# S52.net
KiCad netlist of a schematic drawn in Altium Designer
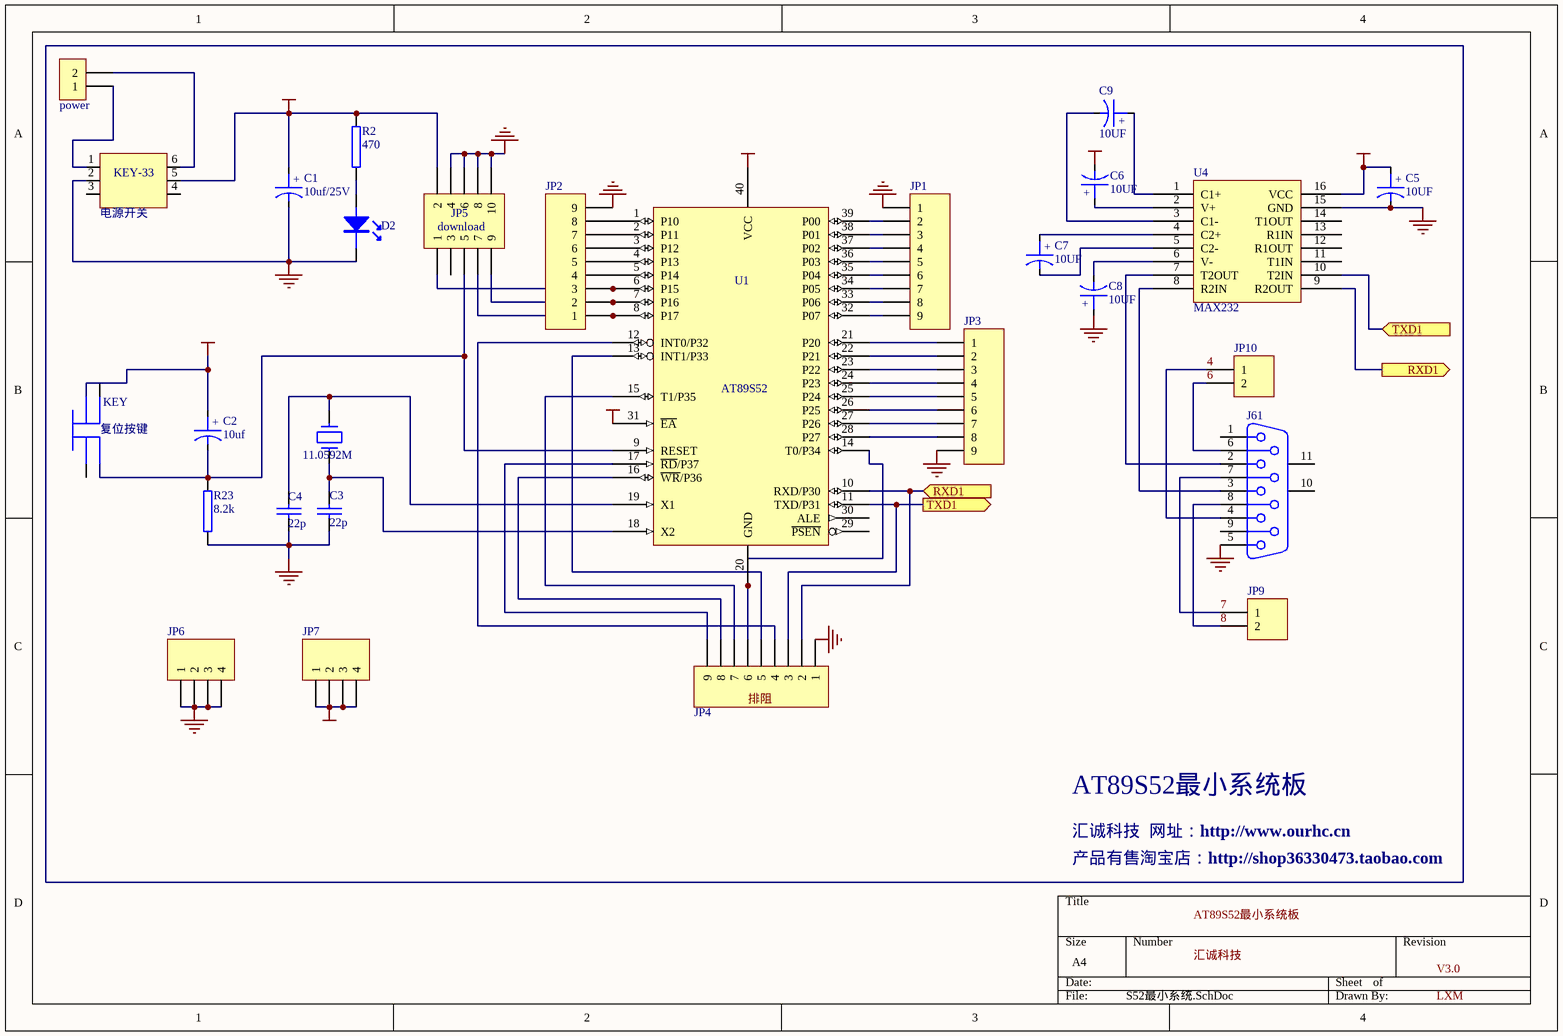
[diagram p0: S52最小系统.SchDoc]

(export (version "E")
  (design (tool "Eeschema 10.0.6"))
  (components
    (comp (ref "11") (value "power") (footprint "power1") (libsource (lib "OldCow1 (1)") (part "power")))
    (comp (ref "C1")
      (value "10uf/25V")
      (footprint "cap2")
      (description "Capacitor")
      (libsource (lib "OldCow1 (1)") (part "CAPACITOR POL"))
    )
    (comp (ref "C2")
      (value "10uf")
      (footprint "cap2")
      (description "Capacitor")
      (libsource (lib "*") (part "CAPACITOR POL"))
    )
    (comp (ref "C3")
      (value "22p")
      (footprint "RAD0.3")
      (description "Capacitor")
      (libsource (lib "*") (part "CAP"))
    )
    (comp (ref "C4")
      (value "22p")
      (footprint "RAD0.3")
      (description "Capacitor")
      (libsource (lib "*") (part "CAP"))
    )
    (comp (ref "C5")
      (value "10UF")
      (footprint "cap2")
      (description "Capacitor")
      (libsource (lib "*") (part "CAPACITOR POL"))
    )
    (comp (ref "C6")
      (value "10UF")
      (footprint "cap2")
      (description "Capacitor")
      (libsource (lib "*") (part "CAPACITOR POL"))
    )
    (comp (ref "C7")
      (value "10UF")
      (footprint "cap2")
      (description "Capacitor")
      (libsource (lib "*") (part "CAPACITOR POL"))
    )
    (comp (ref "C8")
      (value "10UF")
      (footprint "cap2")
      (description "Capacitor")
      (libsource (lib "*") (part "CAPACITOR POL"))
    )
    (comp (ref "C9")
      (value "10UF")
      (footprint "cap2")
      (description "Capacitor")
      (libsource (lib "*") (part "CAPACITOR POL"))
    )
    (comp (ref "D2") (value "LED") (footprint "LED") (libsource (lib "OldCow1 (1)") (part "LED")))
    (comp (ref "J61")
      (value "D Connector 9")
      (footprint "DSUB1.385-2H9")
      (description "Receptacle Assembly, 9 Position, Right Angle")
      (fields (field (name "PUBLISHER") "Altium Limited"))
      (libsource (lib "Miscellaneous Connectors") (part "D Connector 9"))
    )
    (comp (ref "JP1")
      (value "~")
      (footprint "HDR1X9")
      (description "Header, 9-Pin")
      (fields (field (name "PUBLISHER") "Altium Limited"))
      (libsource (lib "") (part "Header 9_2"))
    )
    (comp (ref "JP2")
      (value "~")
      (footprint "HDR1X9")
      (description "Header, 9-Pin")
      (fields (field (name "PUBLISHER") "Altium Limited"))
      (libsource (lib "") (part "Header 9_1"))
    )
    (comp (ref "JP3")
      (value "~")
      (footprint "HDR1X9")
      (description "Header, 9-Pin")
      (fields (field (name "PUBLISHER") "Altium Limited"))
      (libsource (lib "") (part "Header 9_2"))
    )
    (comp (ref "JP4")
      (value "~")
      (footprint "HDR1X9")
      (description "Header, 9-Pin")
      (fields (field (name "PUBLISHER") "Altium Limited"))
      (libsource (lib "Miscellaneous Connectors") (part "Header 9"))
    )
    (comp (ref "JP5")
      (value "download")
      (footprint "HDR2X5")
      (description "Header, 5-Pin, Dual row")
      (fields (field (name "PUBLISHER") "Altium Limited"))
      (libsource (lib "Miscellaneous Connectors") (part "Header 5X2"))
    )
    (comp (ref "JP6")
      (value "~")
      (footprint "HDR1X4")
      (description "Header, 4-Pin")
      (fields (field (name "PUBLISHER") "Altium Limited"))
      (libsource (lib "Miscellaneous Connectors") (part "Header 4"))
    )
    (comp (ref "JP7")
      (value "~")
      (footprint "HDR1X4")
      (description "Header, 4-Pin")
      (fields (field (name "PUBLISHER") "Altium Limited"))
      (libsource (lib "Miscellaneous Connectors") (part "Header 4"))
    )
    (comp (ref "JP9")
      (value "~")
      (footprint "HDR1X2")
      (description "Header, 2-Pin")
      (fields (field (name "PUBLISHER") "Altium Limited"))
      (libsource (lib "Miscellaneous Connectors") (part "Header 2"))
    )
    (comp (ref "JP10")
      (value "Header 3")
      (footprint "HDR1X2")
      (description "Header, 2-Pin")
      (fields (field (name "PUBLISHER") "Altium Limited"))
      (libsource (lib "Miscellaneous Connectors") (part "Header 2"))
    )
    (comp (ref "KEY")
      (value "复位按键")
      (footprint "KEY-1")
      (description "KEY")
      (libsource (lib "OldCow1 (1)") (part "KEY"))
    )
    (comp (ref "KEY-33") (value "电源开关") (footprint "KEY-2") (libsource (lib "OldCow1 (1)") (part "KEY-33")))
    (comp (ref "R2") (value "470") (footprint "AXIAL0.4") (libsource (lib "*") (part "RES2")))
    (comp (ref "R23") (value "8.2k") (footprint "AXIAL0.4") (libsource (lib "*") (part "RES2")))
    (comp (ref "U1") (value "AT89S52") (footprint "AT89S52Pid") (libsource (lib "OldCow1 (2)") (part "8051")))
    (comp (ref "U4") (value "MAX232") (footprint "DIP16") (libsource (lib "*") (part "MAX232")))
    (comp (ref "Y")
      (value "11.0592M")
      (footprint "CRYSTAL")
      (description "Crystal")
      (libsource (lib "*") (part "CRYSTAL"))
    )
  )
  (nets
    (net (code "1") (name "/4") (class "Default")
      (node (ref "J61") (pin "4") (pinfunction "4_4") (pintype "passive"))
      (node (ref "JP10") (pin "1") (pinfunction "1_1") (pintype "passive"))
    )
    (net (code "2") (name "/6") (class "Default")
      (node (ref "J61") (pin "6") (pinfunction "6_6") (pintype "passive"))
      (node (ref "JP10") (pin "2") (pinfunction "2_2") (pintype "passive"))
    )
    (net (code "3") (name "/7") (class "Default")
      (node (ref "J61") (pin "7") (pinfunction "7_7") (pintype "passive"))
      (node (ref "JP9") (pin "1") (pinfunction "1_1") (pintype "passive"))
    )
    (net (code "4") (name "/8") (class "Default")
      (node (ref "J61") (pin "8") (pinfunction "8_8") (pintype "passive"))
      (node (ref "JP9") (pin "2") (pinfunction "2_2") (pintype "passive"))
    )
    (net (code "8") (name "/RXD1") (class "Default")
      (node (ref "JP4") (pin "2") (pinfunction "2_2") (pintype "passive"))
      (node (ref "U1") (pin "10") (pinfunction "RXD/P30_10") (pintype "bidirectional"))
      (node (ref "U4") (pin "9") (pinfunction "R2OUT_9") (pintype "passive"))
    )
    (net (code "9") (name "/TXD1") (class "Default")
      (node (ref "JP4") (pin "3") (pinfunction "3_3") (pintype "passive"))
      (node (ref "U1") (pin "11") (pinfunction "TXD/P31_11") (pintype "bidirectional"))
      (node (ref "U4") (pin "10") (pinfunction "T2IN_10") (pintype "passive"))
    )
    (net (code "13") (name "GND") (class "Default")
      (node (ref "C1") (pin "2") (pinfunction "2_2") (pintype "passive"))
      (node (ref "C3") (pin "2") (pinfunction "2_2") (pintype "passive"))
      (node (ref "C4") (pin "2") (pinfunction "2_2") (pintype "passive"))
      (node (ref "C5") (pin "2") (pinfunction "2_2") (pintype "passive"))
      (node (ref "C8") (pin "1") (pinfunction "1_1") (pintype "passive"))
      (node (ref "D2") (pin "2") (pinfunction "K_2") (pintype "passive"))
      (node (ref "J61") (pin "5") (pinfunction "5_5") (pintype "passive"))
      (node (ref "JP1") (pin "1") (pinfunction "1_1") (pintype "passive"))
      (node (ref "JP2") (pin "9") (pinfunction "9_9") (pintype "passive"))
      (node (ref "JP3") (pin "9") (pinfunction "9_9") (pintype "passive"))
      (node (ref "JP4") (pin "1") (pinfunction "1_1") (pintype "passive"))
      (node (ref "JP5") (pin "10") (pinfunction "10_10") (pintype "passive"))
      (node (ref "JP5") (pin "4") (pinfunction "4_4") (pintype "passive"))
      (node (ref "JP5") (pin "6") (pinfunction "6_6") (pintype "passive"))
      (node (ref "JP5") (pin "8") (pinfunction "8_8") (pintype "passive"))
      (node (ref "JP6") (pin "1") (pinfunction "1_1") (pintype "passive"))
      (node (ref "JP6") (pin "2") (pinfunction "2_2") (pintype "passive"))
      (node (ref "JP6") (pin "3") (pinfunction "3_3") (pintype "passive"))
      (node (ref "JP6") (pin "4") (pinfunction "4_4") (pintype "passive"))
      (node (ref "KEY-33") (pin "2") (pintype "passive"))
      (node (ref "R23") (pin "2") (pinfunction "2_2") (pintype "passive"))
      (node (ref "U4") (pin "15") (pinfunction "GND_15") (pintype "passive"))
    )
    (net (code "14") (name "Net-(11-Pad1)") (class "Default")
      (node (ref "11") (pin "1") (pinfunction "1_1") (pintype "passive"))
      (node (ref "KEY-33") (pin "1") (pintype "passive"))
    )
    (net (code "15") (name "Net-(11-Pad2)") (class "Default")
      (node (ref "11") (pin "2") (pinfunction "2_2") (pintype "passive"))
      (node (ref "KEY-33") (pin "6") (pintype "passive"))
    )
    (net (code "16") (name "Net-(D2-A)") (class "Default")
      (node (ref "D2") (pin "1") (pinfunction "A_1") (pintype "passive"))
      (node (ref "R2") (pin "2") (pinfunction "2_2") (pintype "passive"))
    )
    (net (code "17") (name "Net-(U1-GND)") (class "Default")
      (node (ref "JP4") (pin "6") (pinfunction "6_6") (pintype "passive"))
      (node (ref "U1") (pin "14") (pinfunction "T0/P34_14") (pintype "bidirectional"))
      (node (ref "U1") (pin "20") (pinfunction "GND_20") (pintype "power_in"))
    )
    (net (code "18") (name "Net-(U1-INT0{slash}P32)") (class "Default")
      (node (ref "JP4") (pin "4") (pinfunction "4_4") (pintype "passive"))
      (node (ref "U1") (pin "12") (pinfunction "INT0/P32_12") (pintype "bidirectional"))
    )
    (net (code "19") (name "Net-(U1-INT1{slash}P33)") (class "Default")
      (node (ref "JP4") (pin "5") (pinfunction "5_5") (pintype "passive"))
      (node (ref "U1") (pin "13") (pinfunction "INT1/P33_13") (pintype "bidirectional"))
    )
    (net (code "20") (name "Net-(U1-P00)") (class "Default")
      (node (ref "JP1") (pin "2") (pinfunction "2_2") (pintype "passive"))
      (node (ref "U1") (pin "39") (pinfunction "P00_39") (pintype "bidirectional"))
    )
    (net (code "21") (name "Net-(U1-P01)") (class "Default")
      (node (ref "JP1") (pin "3") (pinfunction "3_3") (pintype "passive"))
      (node (ref "U1") (pin "38") (pinfunction "P01_38") (pintype "bidirectional"))
    )
    (net (code "22") (name "Net-(U1-P02)") (class "Default")
      (node (ref "JP1") (pin "4") (pinfunction "4_4") (pintype "passive"))
      (node (ref "U1") (pin "37") (pinfunction "P02_37") (pintype "bidirectional"))
    )
    (net (code "23") (name "Net-(U1-P03)") (class "Default")
      (node (ref "JP1") (pin "5") (pinfunction "5_5") (pintype "passive"))
      (node (ref "U1") (pin "36") (pinfunction "P03_36") (pintype "bidirectional"))
    )
    (net (code "24") (name "Net-(U1-P04)") (class "Default")
      (node (ref "JP1") (pin "6") (pinfunction "6_6") (pintype "passive"))
      (node (ref "U1") (pin "35") (pinfunction "P04_35") (pintype "bidirectional"))
    )
    (net (code "25") (name "Net-(U1-P05)") (class "Default")
      (node (ref "JP1") (pin "7") (pinfunction "7_7") (pintype "passive"))
      (node (ref "U1") (pin "34") (pinfunction "P05_34") (pintype "bidirectional"))
    )
    (net (code "26") (name "Net-(U1-P06)") (class "Default")
      (node (ref "JP1") (pin "8") (pinfunction "8_8") (pintype "passive"))
      (node (ref "U1") (pin "33") (pinfunction "P06_33") (pintype "bidirectional"))
    )
    (net (code "27") (name "Net-(U1-P07)") (class "Default")
      (node (ref "JP1") (pin "9") (pinfunction "9_9") (pintype "passive"))
      (node (ref "U1") (pin "32") (pinfunction "P07_32") (pintype "bidirectional"))
    )
    (net (code "28") (name "Net-(U1-P10)") (class "Default")
      (node (ref "JP2") (pin "8") (pinfunction "8_8") (pintype "passive"))
      (node (ref "U1") (pin "1") (pinfunction "P10_1") (pintype "bidirectional"))
    )
    (net (code "29") (name "Net-(U1-P11)") (class "Default")
      (node (ref "JP2") (pin "7") (pinfunction "7_7") (pintype "passive"))
      (node (ref "U1") (pin "2") (pinfunction "P11_2") (pintype "bidirectional"))
    )
    (net (code "30") (name "Net-(U1-P12)") (class "Default")
      (node (ref "JP2") (pin "6") (pinfunction "6_6") (pintype "passive"))
      (node (ref "U1") (pin "3") (pinfunction "P12_3") (pintype "bidirectional"))
    )
    (net (code "31") (name "Net-(U1-P13)") (class "Default")
      (node (ref "JP2") (pin "5") (pinfunction "5_5") (pintype "passive"))
      (node (ref "U1") (pin "4") (pinfunction "P13_4") (pintype "bidirectional"))
    )
    (net (code "32") (name "Net-(U1-P14)") (class "Default")
      (node (ref "JP2") (pin "4") (pinfunction "4_4") (pintype "passive"))
      (node (ref "U1") (pin "5") (pinfunction "P14_5") (pintype "bidirectional"))
    )
    (net (code "33") (name "Net-(U1-P15)") (class "Default")
      (node (ref "JP2") (pin "3") (pinfunction "3_3") (pintype "passive"))
      (node (ref "JP5") (pin "1") (pinfunction "1_1") (pintype "passive"))
      (node (ref "U1") (pin "6") (pinfunction "P15_6") (pintype "bidirectional"))
    )
    (net (code "34") (name "Net-(U1-P16)") (class "Default")
      (node (ref "JP2") (pin "2") (pinfunction "2_2") (pintype "passive"))
      (node (ref "JP5") (pin "9") (pinfunction "9_9") (pintype "passive"))
      (node (ref "U1") (pin "7") (pinfunction "P16_7") (pintype "bidirectional"))
    )
    (net (code "35") (name "Net-(U1-P17)") (class "Default")
      (node (ref "JP2") (pin "1") (pinfunction "1_1") (pintype "passive"))
      (node (ref "JP5") (pin "7") (pinfunction "7_7") (pintype "passive"))
      (node (ref "U1") (pin "8") (pinfunction "P17_8") (pintype "bidirectional"))
    )
    (net (code "36") (name "Net-(U1-P20)") (class "Default")
      (node (ref "JP3") (pin "1") (pinfunction "1_1") (pintype "passive"))
      (node (ref "U1") (pin "21") (pinfunction "P20_21") (pintype "bidirectional"))
    )
    (net (code "37") (name "Net-(U1-P21)") (class "Default")
      (node (ref "JP3") (pin "2") (pinfunction "2_2") (pintype "passive"))
      (node (ref "U1") (pin "22") (pinfunction "P21_22") (pintype "bidirectional"))
    )
    (net (code "38") (name "Net-(U1-P22)") (class "Default")
      (node (ref "JP3") (pin "3") (pinfunction "3_3") (pintype "passive"))
      (node (ref "U1") (pin "23") (pinfunction "P22_23") (pintype "bidirectional"))
    )
    (net (code "39") (name "Net-(U1-P23)") (class "Default")
      (node (ref "JP3") (pin "4") (pinfunction "4_4") (pintype "passive"))
      (node (ref "U1") (pin "24") (pinfunction "P23_24") (pintype "bidirectional"))
    )
    (net (code "40") (name "Net-(U1-P24)") (class "Default")
      (node (ref "JP3") (pin "5") (pinfunction "5_5") (pintype "passive"))
      (node (ref "U1") (pin "25") (pinfunction "P24_25") (pintype "bidirectional"))
    )
    (net (code "41") (name "Net-(U1-P25)") (class "Default")
      (node (ref "JP3") (pin "6") (pinfunction "6_6") (pintype "passive"))
      (node (ref "U1") (pin "26") (pinfunction "P25_26") (pintype "bidirectional"))
    )
    (net (code "42") (name "Net-(U1-P26)") (class "Default")
      (node (ref "JP3") (pin "7") (pinfunction "7_7") (pintype "passive"))
      (node (ref "U1") (pin "27") (pinfunction "P26_27") (pintype "bidirectional"))
    )
    (net (code "43") (name "Net-(U1-P27)") (class "Default")
      (node (ref "JP3") (pin "8") (pinfunction "8_8") (pintype "passive"))
      (node (ref "U1") (pin "28") (pinfunction "P27_28") (pintype "bidirectional"))
    )
    (net (code "44") (name "Net-(U1-RESET)") (class "Default")
      (node (ref "C2") (pin "2") (pinfunction "2_2") (pintype "passive"))
      (node (ref "JP5") (pin "5") (pinfunction "5_5") (pintype "passive"))
      (node (ref "KEY") (pin "2") (pinfunction "2_2") (pintype "passive"))
      (node (ref "R23") (pin "1") (pinfunction "1_1") (pintype "passive"))
      (node (ref "U1") (pin "9") (pinfunction "RESET_9") (pintype "input"))
    )
    (net (code "45") (name "Net-(U1-T1{slash}P35)") (class "Default")
      (node (ref "JP4") (pin "7") (pinfunction "7_7") (pintype "passive"))
      (node (ref "U1") (pin "15") (pinfunction "T1/P35_15") (pintype "bidirectional"))
    )
    (net (code "46") (name "Net-(U1-X1)") (class "Default")
      (node (ref "C4") (pin "1") (pinfunction "1_1") (pintype "passive"))
      (node (ref "U1") (pin "19") (pinfunction "X1_19") (pintype "input"))
      (node (ref "Y") (pin "1") (pinfunction "1_1") (pintype "passive"))
    )
    (net (code "47") (name "Net-(U1-X2)") (class "Default")
      (node (ref "C3") (pin "1") (pinfunction "1_1") (pintype "passive"))
      (node (ref "U1") (pin "18") (pinfunction "X2_18") (pintype "input"))
      (node (ref "Y") (pin "2") (pinfunction "2_2") (pintype "passive"))
    )
    (net (code "48") (name "Net-(U1-~{RD}{slash}P37)") (class "Default")
      (node (ref "JP4") (pin "9") (pinfunction "9_9") (pintype "passive"))
      (node (ref "U1") (pin "17") (pinfunction "~{RD}/P37_17") (pintype "input"))
    )
    (net (code "49") (name "Net-(U1-~{WR}{slash}P36)") (class "Default")
      (node (ref "JP4") (pin "8") (pinfunction "8_8") (pintype "passive"))
      (node (ref "U1") (pin "16") (pinfunction "~{WR}/P36_16") (pintype "bidirectional"))
    )
    (net (code "50") (name "Net-(U4-C1+)") (class "Default")
      (node (ref "C9") (pin "1") (pinfunction "1_1") (pintype "passive"))
      (node (ref "U4") (pin "1") (pinfunction "C1+_1") (pintype "passive"))
    )
    (net (code "51") (name "Net-(U4-C1-)") (class "Default")
      (node (ref "C9") (pin "2") (pinfunction "2_2") (pintype "passive"))
      (node (ref "U4") (pin "3") (pinfunction "C1-_3") (pintype "passive"))
    )
    (net (code "52") (name "Net-(U4-C2+)") (class "Default")
      (node (ref "C7") (pin "1") (pinfunction "1_1") (pintype "passive"))
      (node (ref "U4") (pin "4") (pinfunction "C2+_4") (pintype "passive"))
    )
    (net (code "53") (name "Net-(U4-C2-)") (class "Default")
      (node (ref "C7") (pin "2") (pinfunction "2_2") (pintype "passive"))
      (node (ref "U4") (pin "5") (pinfunction "C2-_5") (pintype "passive"))
    )
    (net (code "54") (name "Net-(U4-R2IN)") (class "Default")
      (node (ref "J61") (pin "3") (pinfunction "3_3") (pintype "passive"))
      (node (ref "U4") (pin "8") (pinfunction "R2IN_8") (pintype "passive"))
    )
    (net (code "55") (name "Net-(U4-T2OUT)") (class "Default")
      (node (ref "J61") (pin "2") (pinfunction "2_2") (pintype "passive"))
      (node (ref "U4") (pin "7") (pinfunction "T2OUT_7") (pintype "passive"))
    )
    (net (code "56") (name "Net-(U4-V+)") (class "Default")
      (node (ref "C6") (pin "1") (pinfunction "1_1") (pintype "passive"))
      (node (ref "U4") (pin "2") (pinfunction "V+_2") (pintype "passive"))
    )
    (net (code "57") (name "Net-(U4-V-)") (class "Default")
      (node (ref "C8") (pin "2") (pinfunction "2_2") (pintype "passive"))
      (node (ref "U4") (pin "6") (pinfunction "V-_6") (pintype "passive"))
    )
    (net (code "58") (name "VCC") (class "Default")
      (node (ref "C1") (pin "1") (pinfunction "1_1") (pintype "passive"))
      (node (ref "C2") (pin "1") (pinfunction "1_1") (pintype "passive"))
      (node (ref "C5") (pin "1") (pinfunction "1_1") (pintype "passive"))
      (node (ref "C6") (pin "2") (pinfunction "2_2") (pintype "passive"))
      (node (ref "JP5") (pin "2") (pinfunction "2_2") (pintype "passive"))
      (node (ref "JP7") (pin "1") (pinfunction "1_1") (pintype "passive"))
      (node (ref "JP7") (pin "2") (pinfunction "2_2") (pintype "passive"))
      (node (ref "JP7") (pin "3") (pinfunction "3_3") (pintype "passive"))
      (node (ref "JP7") (pin "4") (pinfunction "4_4") (pintype "passive"))
      (node (ref "KEY") (pin "1") (pinfunction "1_1") (pintype "passive"))
      (node (ref "KEY-33") (pin "5") (pintype "passive"))
      (node (ref "R2") (pin "1") (pinfunction "1_1") (pintype "passive"))
      (node (ref "U1") (pin "31") (pinfunction "~{EA}_31") (pintype "input"))
      (node (ref "U1") (pin "40") (pinfunction "VCC_40") (pintype "power_in"))
      (node (ref "U4") (pin "16") (pinfunction "VCC_16") (pintype "passive"))
    )
    (net (code "59") (name "unconnected-(J61-MH1-Pad10)") (class "Default")
      (node (ref "J61") (pin "10") (pinfunction "MH1_10") (pintype "passive"))
    )
    (net (code "60") (name "unconnected-(J61-MH2-Pad11)") (class "Default")
      (node (ref "J61") (pin "11") (pinfunction "MH2_11") (pintype "passive"))
    )
    (net (code "61") (name "unconnected-(J61-Pad1)") (class "Default")
      (node (ref "J61") (pin "1") (pinfunction "1_1") (pintype "passive"))
    )
    (net (code "62") (name "unconnected-(J61-Pad9)") (class "Default")
      (node (ref "J61") (pin "9") (pinfunction "9_9") (pintype "passive"))
    )
    (net (code "63") (name "unconnected-(JP5-Pad3)") (class "Default")
      (node (ref "JP5") (pin "3") (pinfunction "3_3") (pintype "passive"))
    )
    (net (code "64") (name "unconnected-(KEY-33-Pad3)") (class "Default")
      (node (ref "KEY-33") (pin "3") (pintype "passive"))
    )
    (net (code "65") (name "unconnected-(KEY-33-Pad4)") (class "Default")
      (node (ref "KEY-33") (pin "4") (pintype "passive"))
    )
    (net (code "66") (name "unconnected-(KEY-Pad0)") (class "Default")
      (node (ref "KEY") (pin "0") (pinfunction "0_0") (pintype "passive"))
    )
    (net (code "67") (name "unconnected-(KEY-Pad3)") (class "Default")
      (node (ref "KEY") (pin "3") (pinfunction "3_3") (pintype "passive"))
    )
    (net (code "68") (name "unconnected-(U1-ALE-Pad30)") (class "Default")
      (node (ref "U1") (pin "30") (pinfunction "ALE_30") (pintype "output"))
    )
    (net (code "69") (name "unconnected-(U1-~{PSEN}-Pad29)") (class "Default")
      (node (ref "U1") (pin "29") (pinfunction "~{PSEN}_29") (pintype "output"))
    )
    (net (code "70") (name "unconnected-(U4-R1IN-Pad13)") (class "Default")
      (node (ref "U4") (pin "13") (pinfunction "R1IN_13") (pintype "passive"))
    )
    (net (code "71") (name "unconnected-(U4-R1OUT-Pad12)") (class "Default")
      (node (ref "U4") (pin "12") (pinfunction "R1OUT_12") (pintype "passive"))
    )
    (net (code "72") (name "unconnected-(U4-T1IN-Pad11)") (class "Default")
      (node (ref "U4") (pin "11") (pinfunction "T1IN_11") (pintype "passive"))
    )
    (net (code "73") (name "unconnected-(U4-T1OUT-Pad14)") (class "Default")
      (node (ref "U4") (pin "14") (pinfunction "T1OUT_14") (pintype "passive"))
    )
  )
)
